# Qwiic_1_8V_Adapter.net
KiCad netlist of a schematic drawn in EAGLE
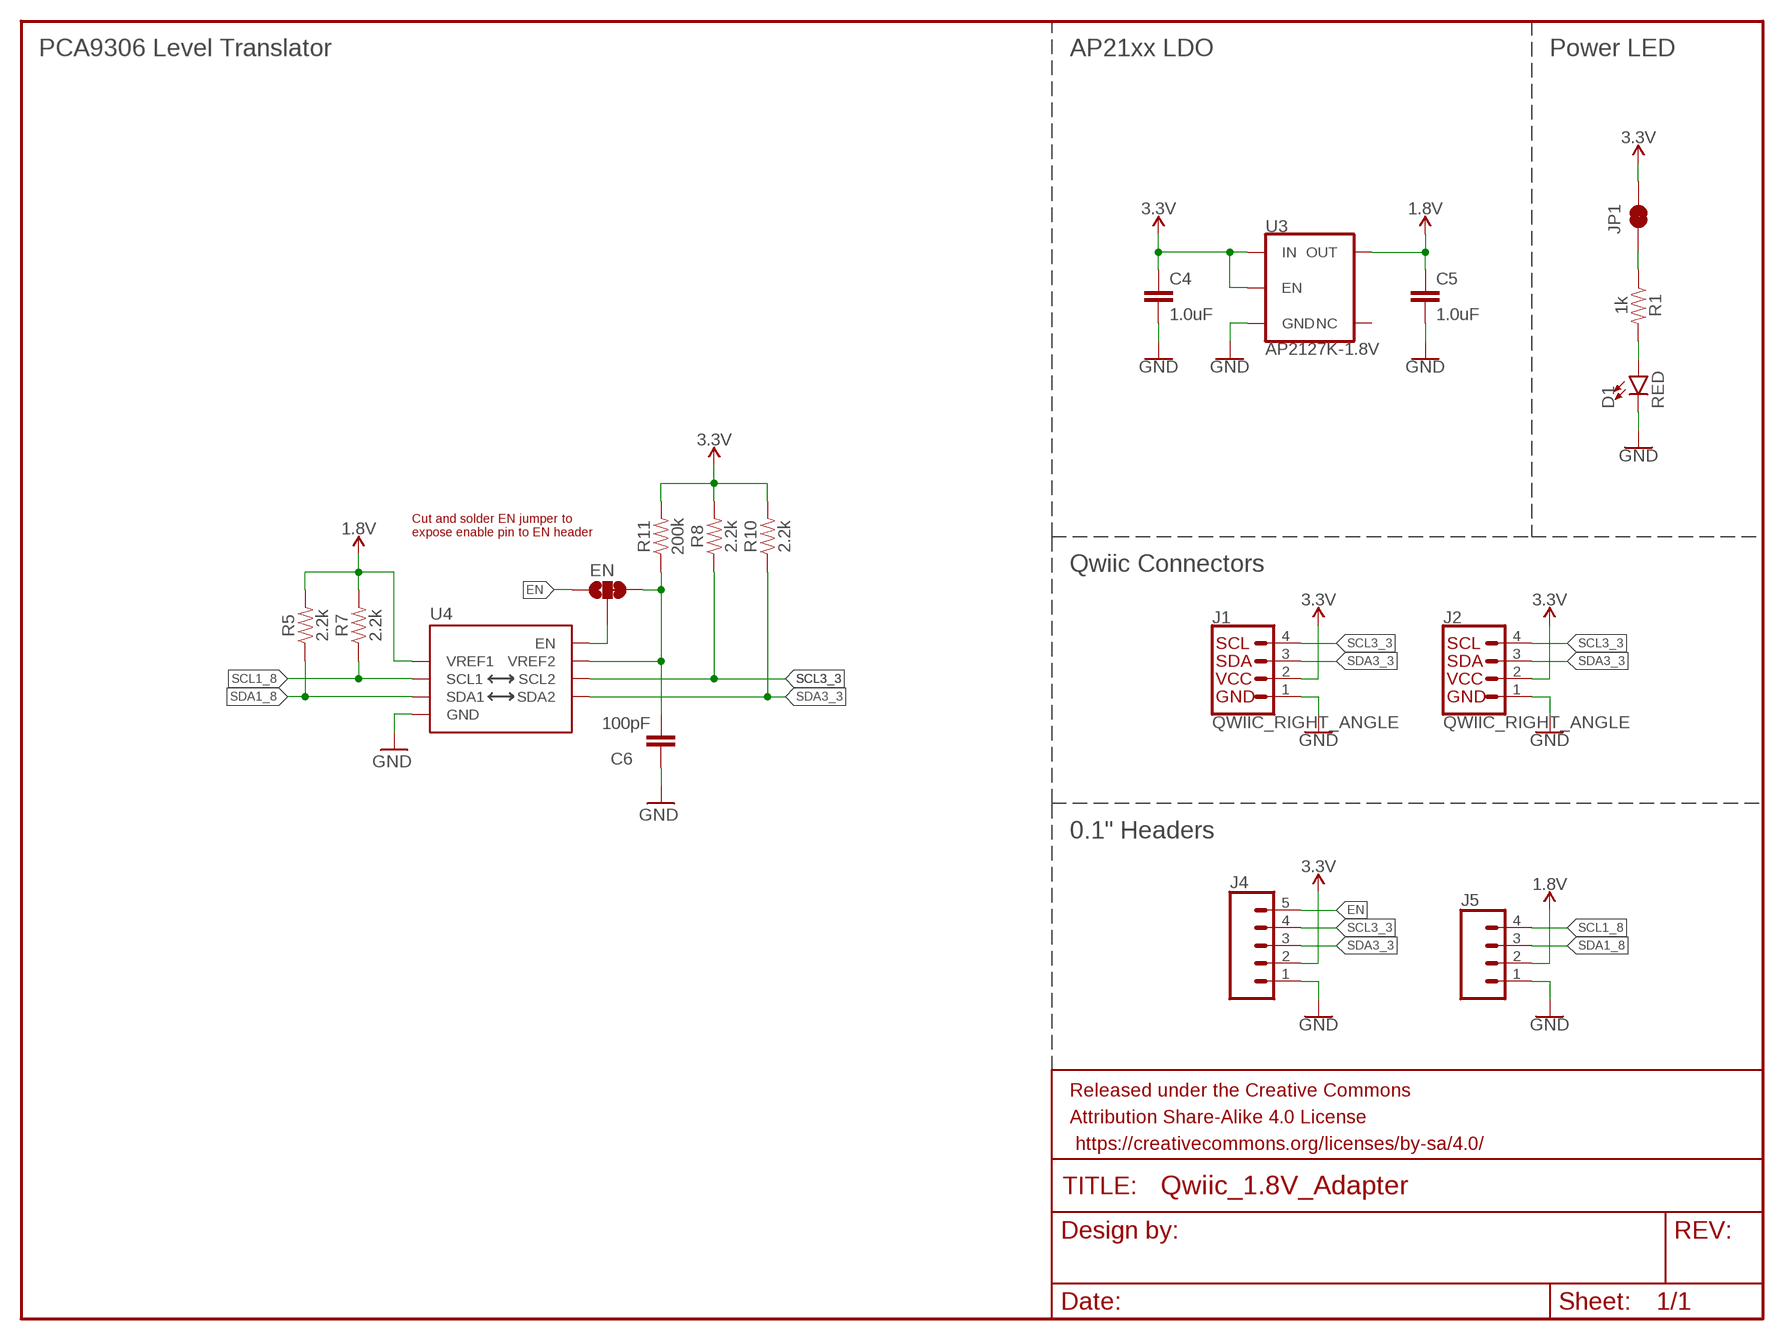
[diagram p0: schematic, sheet 1]

(export (version "E")
  (design (tool "Eeschema 10.0.6"))
  (components
    (comp (ref "C4")
      (value "1.0uF")
      (footprint "eagle-import:0603")
      (libsource (lib "eagle-import") (part "1.0UF-0603-16V-10%"))
    )
    (comp (ref "C5")
      (value "1.0uF")
      (footprint "eagle-import:0603")
      (libsource (lib "eagle-import") (part "1.0UF-0603-16V-10%"))
    )
    (comp (ref "C6")
      (value "100pF")
      (footprint "eagle-import:0603")
      (libsource (lib "eagle-import") (part "100PF-0603-50V-5%"))
    )
    (comp (ref "D1")
      (value "RED")
      (footprint "eagle-import:LED-0603")
      (libsource (lib "eagle-import") (part "LED-RED0603"))
    )
    (comp (ref "EN")
      (value "JUMPER-SMT_3_1-NC_TRACE_SILK")
      (footprint "eagle-import:SMT-JUMPER_3_1-NC_TRACE_SILK")
      (libsource (lib "eagle-import") (part "JUMPER-SMT_3_1-NC_TRACE_SILK"))
    )
    (comp (ref "FRAME1")
      (value "FRAME-LETTER")
      (footprint "eagle-import:CREATIVE_COMMONS")
      (libsource (lib "eagle-import") (part "FRAME-LETTER"))
    )
    (comp (ref "J1")
      (value "QWIIC_RIGHT_ANGLE")
      (footprint "eagle-import:JST04_1MM_RA")
      (libsource (lib "eagle-import") (part "QWIIC_CONNECTORJS-1MM"))
    )
    (comp (ref "J2")
      (value "QWIIC_RIGHT_ANGLE")
      (footprint "eagle-import:JST04_1MM_RA")
      (libsource (lib "eagle-import") (part "QWIIC_CONNECTORJS-1MM"))
    )
    (comp (ref "J4")
      (value "CONN_05NO_SILK")
      (footprint "eagle-import:1X05_NO_SILK")
      (libsource (lib "eagle-import") (part "CONN_05NO_SILK"))
    )
    (comp (ref "J5")
      (value "CONN_041X04_NO_SILK")
      (footprint "eagle-import:1X04_NO_SILK")
      (libsource (lib "eagle-import") (part "CONN_041X04_NO_SILK"))
    )
    (comp (ref "JP1")
      (value "JUMPER-SMT_2_NC_TRACE_SILK")
      (footprint "eagle-import:SMT-JUMPER_2_NC_TRACE_SILK")
      (libsource (lib "eagle-import") (part "JUMPER-SMT_2_NC_TRACE_SILK"))
    )
    (comp (ref "R1")
      (value "1k")
      (footprint "eagle-import:0603")
      (libsource (lib "eagle-import") (part "1KOHM-0603-1/10W-1%"))
    )
    (comp (ref "R5")
      (value "2.2k")
      (footprint "eagle-import:0603")
      (libsource (lib "eagle-import") (part "2.2KOHM-0603-1/10W-1%"))
    )
    (comp (ref "R7")
      (value "2.2k")
      (footprint "eagle-import:0603")
      (libsource (lib "eagle-import") (part "2.2KOHM-0603-1/10W-1%"))
    )
    (comp (ref "R8")
      (value "2.2k")
      (footprint "eagle-import:0603")
      (libsource (lib "eagle-import") (part "2.2KOHM-0603-1/10W-1%"))
    )
    (comp (ref "R10")
      (value "2.2k")
      (footprint "eagle-import:0603")
      (libsource (lib "eagle-import") (part "2.2KOHM-0603-1/10W-1%"))
    )
    (comp (ref "R11")
      (value "200k")
      (footprint "eagle-import:0603")
      (libsource (lib "eagle-import") (part "200KOHM-0603-1/10W-1%"))
    )
    (comp (ref "U3")
      (value "AP2127K-1.8V")
      (footprint "eagle-import:SOT23-5")
      (libsource (lib "eagle-import") (part "V_REG_AP2127K-1.8V"))
    )
    (comp (ref "U4")
      (value "PCA9306VSSOP_8PIN")
      (footprint "eagle-import:VSSOP_8PIN")
      (libsource (lib "eagle-import") (part "PCA9306VSSOP_8PIN"))
    )
  )
  (nets
    (net (code "1") (name "1.8V") (class "Default")
      (node (ref "C5") (pin "1") (pinfunction "1_1") (pintype "passive"))
      (node (ref "J5") (pin "2") (pinfunction "2_2") (pintype "passive"))
      (node (ref "R5") (pin "2") (pinfunction "2_2") (pintype "passive"))
      (node (ref "R7") (pin "2") (pinfunction "2_2") (pintype "passive"))
      (node (ref "U3") (pin "5") (pinfunction "OUT_5") (pintype "passive"))
      (node (ref "U4") (pin "P2") (pinfunction "VREF1_P2") (pintype "power_in"))
    )
    (net (code "2") (name "3.3V") (class "Default")
      (node (ref "C4") (pin "1") (pinfunction "1_1") (pintype "passive"))
      (node (ref "J1") (pin "2") (pinfunction "2_2") (pintype "power_in"))
      (node (ref "J2") (pin "2") (pinfunction "2_2") (pintype "power_in"))
      (node (ref "J4") (pin "2") (pinfunction "2_2") (pintype "passive"))
      (node (ref "JP1") (pin "2") (pinfunction "2_2") (pintype "passive"))
      (node (ref "R10") (pin "2") (pinfunction "2_2") (pintype "passive"))
      (node (ref "R11") (pin "2") (pinfunction "2_2") (pintype "passive"))
      (node (ref "R8") (pin "2") (pinfunction "2_2") (pintype "passive"))
      (node (ref "U3") (pin "1") (pinfunction "IN_1") (pintype "input"))
      (node (ref "U3") (pin "3") (pinfunction "EN_3") (pintype "input"))
    )
    (net (code "3") (name "EN") (class "Default")
      (node (ref "EN") (pin "1") (pinfunction "1_1") (pintype "passive"))
      (node (ref "J4") (pin "5") (pinfunction "5_5") (pintype "passive"))
    )
    (net (code "4") (name "GND") (class "Default")
      (node (ref "C4") (pin "2") (pinfunction "2_2") (pintype "passive"))
      (node (ref "C5") (pin "2") (pinfunction "2_2") (pintype "passive"))
      (node (ref "C6") (pin "1") (pinfunction "1_1") (pintype "passive"))
      (node (ref "D1") (pin "C") (pinfunction "C_C") (pintype "passive"))
      (node (ref "J1") (pin "1") (pinfunction "1_1") (pintype "power_in"))
      (node (ref "J2") (pin "1") (pinfunction "1_1") (pintype "power_in"))
      (node (ref "J4") (pin "1") (pinfunction "1_1") (pintype "passive"))
      (node (ref "J5") (pin "1") (pinfunction "1_1") (pintype "passive"))
      (node (ref "U3") (pin "2") (pinfunction "GND_2") (pintype "input"))
      (node (ref "U4") (pin "P1") (pinfunction "GND_P1") (pintype "power_in"))
    )
    (net (code "5") (name "Net-(D1-PadA)") (class "Default")
      (node (ref "D1") (pin "A") (pinfunction "A_A") (pintype "passive"))
      (node (ref "R1") (pin "2") (pinfunction "2_2") (pintype "passive"))
    )
    (net (code "6") (name "Net-(JP1-Pad1)") (class "Default")
      (node (ref "JP1") (pin "1") (pinfunction "1_1") (pintype "passive"))
      (node (ref "R1") (pin "1") (pinfunction "1_1") (pintype "passive"))
    )
    (net (code "7") (name "Net-(U4-EN)") (class "Default")
      (node (ref "EN") (pin "2") (pinfunction "2_2") (pintype "passive"))
      (node (ref "U4") (pin "P8") (pinfunction "EN_P8") (pintype "input"))
    )
    (net (code "8") (name "Net-(U4-VREF2)") (class "Default")
      (node (ref "C6") (pin "2") (pinfunction "2_2") (pintype "passive"))
      (node (ref "EN") (pin "3") (pinfunction "3_3") (pintype "passive"))
      (node (ref "R11") (pin "1") (pinfunction "1_1") (pintype "passive"))
      (node (ref "U4") (pin "P7") (pinfunction "VREF2_P7") (pintype "power_in"))
    )
    (net (code "9") (name "SCL1_8") (class "Default")
      (node (ref "J5") (pin "4") (pinfunction "4_4") (pintype "passive"))
      (node (ref "R7") (pin "1") (pinfunction "1_1") (pintype "passive"))
      (node (ref "U4") (pin "P3") (pinfunction "SCL1_P3") (pintype "bidirectional"))
    )
    (net (code "10") (name "SCL3_3") (class "Default")
      (node (ref "J1") (pin "4") (pinfunction "4_4") (pintype "passive"))
      (node (ref "J2") (pin "4") (pinfunction "4_4") (pintype "passive"))
      (node (ref "J4") (pin "4") (pinfunction "4_4") (pintype "passive"))
      (node (ref "R8") (pin "1") (pinfunction "1_1") (pintype "passive"))
      (node (ref "U4") (pin "P6") (pinfunction "SCL2_P6") (pintype "bidirectional"))
    )
    (net (code "11") (name "SDA1_8") (class "Default")
      (node (ref "J5") (pin "3") (pinfunction "3_3") (pintype "passive"))
      (node (ref "R5") (pin "1") (pinfunction "1_1") (pintype "passive"))
      (node (ref "U4") (pin "P4") (pinfunction "SDA1_P4") (pintype "bidirectional"))
    )
    (net (code "12") (name "SDA3_3") (class "Default")
      (node (ref "J1") (pin "3") (pinfunction "3_3") (pintype "passive"))
      (node (ref "J2") (pin "3") (pinfunction "3_3") (pintype "passive"))
      (node (ref "J4") (pin "3") (pinfunction "3_3") (pintype "passive"))
      (node (ref "R10") (pin "1") (pinfunction "1_1") (pintype "passive"))
      (node (ref "U4") (pin "P5") (pinfunction "SDA2_P5") (pintype "bidirectional"))
    )
    (net (code "13") (name "unconnected-(U3-NC-Pad4)") (class "Default")
      (node (ref "U3") (pin "4") (pinfunction "NC_4") (pintype "no_connect"))
    )
  )
)
